# x-.net
KiCad netlist of a schematic drawn in Altium Designer
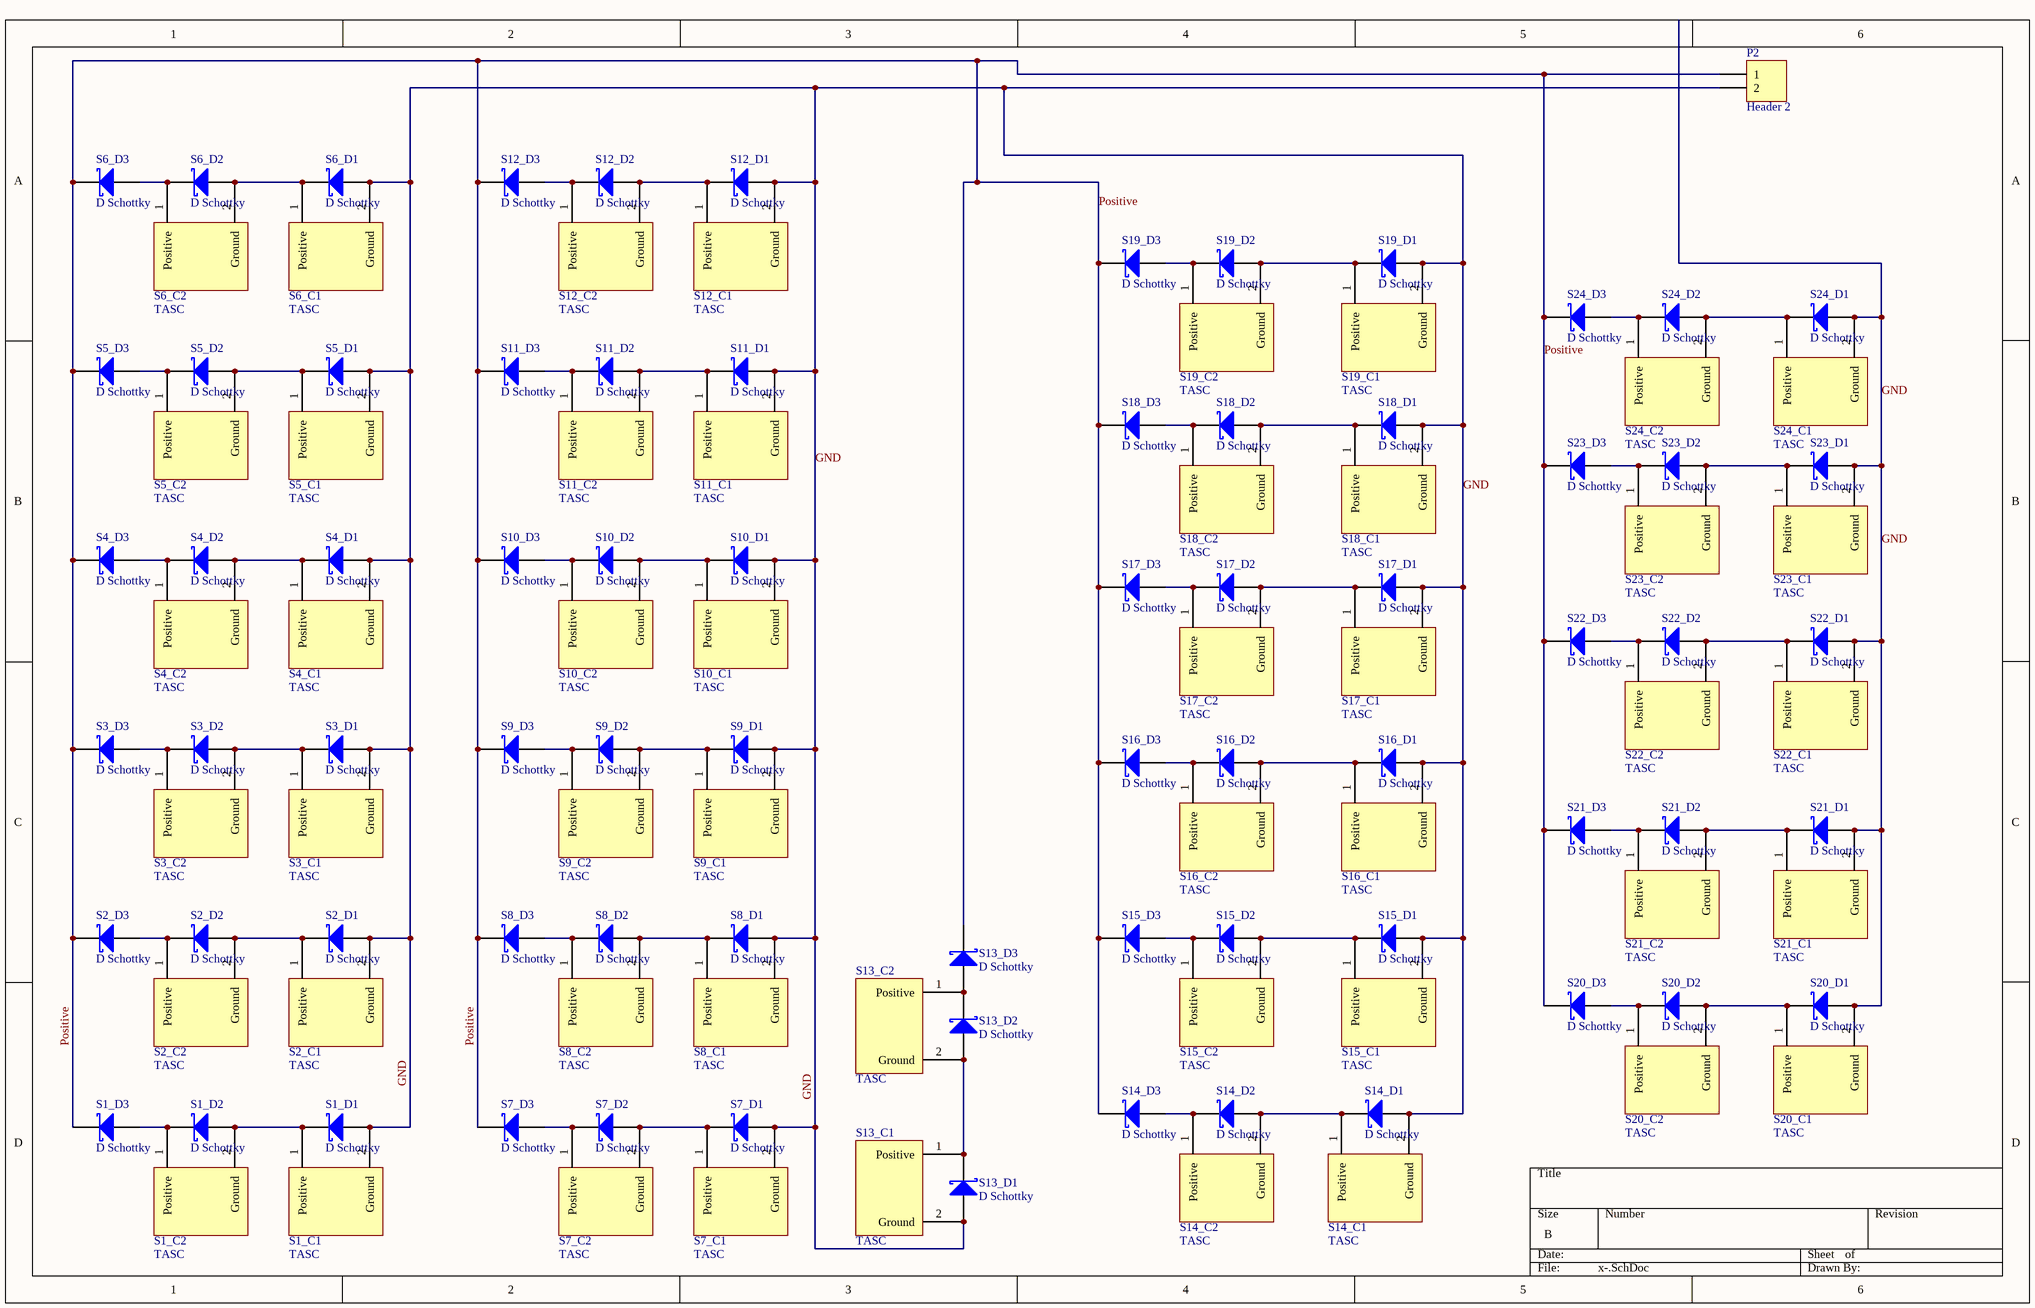
[diagram p0: x-.SchDoc]

(export (version "E")
  (design (tool "Eeschema 10.0.6"))
  (components
    (comp (ref "P2")
      (value "Header 2")
      (footprint "HDR1X2")
      (description "Header, 2-Pin")
      (fields (field (name "PUBLISHER") "Altium Limited"))
      (libsource (lib "Miscellaneous Connectors") (part "Header 2"))
    )
    (comp (ref "S1_C1")
      (value "TASC")
      (footprint "PCBComponent_1")
      (description "TASC Solar Cell")
      (libsource (lib "SolarPanel1") (part "TASC"))
    )
    (comp (ref "S1_C2")
      (value "TASC")
      (footprint "PCBComponent_1")
      (description "TASC Solar Cell")
      (libsource (lib "SolarPanel1") (part "TASC"))
    )
    (comp (ref "S1_D1")
      (value "D Schottky")
      (footprint "SMB")
      (description "Schottky Diode")
      (fields (field (name "PUBLISHER") "Altium Limited"))
      (libsource (lib "Miscellaneous Devices") (part "D Schottky"))
    )
    (comp (ref "S1_D2")
      (value "D Schottky")
      (footprint "SMB")
      (description "Schottky Diode")
      (fields (field (name "PUBLISHER") "Altium Limited"))
      (libsource (lib "Miscellaneous Devices") (part "D Schottky"))
    )
    (comp (ref "S1_D3")
      (value "D Schottky")
      (footprint "SMB")
      (description "Schottky Diode")
      (fields (field (name "PUBLISHER") "Altium Limited"))
      (libsource (lib "Miscellaneous Devices") (part "D Schottky"))
    )
    (comp (ref "S2_C1")
      (value "TASC")
      (footprint "PCBComponent_1")
      (description "TASC Solar Cell")
      (libsource (lib "SolarPanel1") (part "TASC"))
    )
    (comp (ref "S2_C2")
      (value "TASC")
      (footprint "PCBComponent_1")
      (description "TASC Solar Cell")
      (libsource (lib "SolarPanel1") (part "TASC"))
    )
    (comp (ref "S2_D1")
      (value "D Schottky")
      (footprint "SMB")
      (description "Schottky Diode")
      (fields (field (name "PUBLISHER") "Altium Limited"))
      (libsource (lib "Miscellaneous Devices") (part "D Schottky"))
    )
    (comp (ref "S2_D2")
      (value "D Schottky")
      (footprint "SMB")
      (description "Schottky Diode")
      (fields (field (name "PUBLISHER") "Altium Limited"))
      (libsource (lib "Miscellaneous Devices") (part "D Schottky"))
    )
    (comp (ref "S2_D3")
      (value "D Schottky")
      (footprint "SMB")
      (description "Schottky Diode")
      (fields (field (name "PUBLISHER") "Altium Limited"))
      (libsource (lib "Miscellaneous Devices") (part "D Schottky"))
    )
    (comp (ref "S3_C1")
      (value "TASC")
      (footprint "PCBComponent_1")
      (description "TASC Solar Cell")
      (libsource (lib "SolarPanel1") (part "TASC"))
    )
    (comp (ref "S3_C2")
      (value "TASC")
      (footprint "PCBComponent_1")
      (description "TASC Solar Cell")
      (libsource (lib "SolarPanel1") (part "TASC"))
    )
    (comp (ref "S3_D1")
      (value "D Schottky")
      (footprint "SMB")
      (description "Schottky Diode")
      (fields (field (name "PUBLISHER") "Altium Limited"))
      (libsource (lib "Miscellaneous Devices") (part "D Schottky"))
    )
    (comp (ref "S3_D2")
      (value "D Schottky")
      (footprint "SMB")
      (description "Schottky Diode")
      (fields (field (name "PUBLISHER") "Altium Limited"))
      (libsource (lib "Miscellaneous Devices") (part "D Schottky"))
    )
    (comp (ref "S3_D3")
      (value "D Schottky")
      (footprint "SMB")
      (description "Schottky Diode")
      (fields (field (name "PUBLISHER") "Altium Limited"))
      (libsource (lib "Miscellaneous Devices") (part "D Schottky"))
    )
    (comp (ref "S4_C1")
      (value "TASC")
      (footprint "PCBComponent_1")
      (description "TASC Solar Cell")
      (libsource (lib "SolarPanel1") (part "TASC"))
    )
    (comp (ref "S4_C2")
      (value "TASC")
      (footprint "PCBComponent_1")
      (description "TASC Solar Cell")
      (libsource (lib "SolarPanel1") (part "TASC"))
    )
    (comp (ref "S4_D1")
      (value "D Schottky")
      (footprint "SMB")
      (description "Schottky Diode")
      (fields (field (name "PUBLISHER") "Altium Limited"))
      (libsource (lib "Miscellaneous Devices") (part "D Schottky"))
    )
    (comp (ref "S4_D2")
      (value "D Schottky")
      (footprint "SMB")
      (description "Schottky Diode")
      (fields (field (name "PUBLISHER") "Altium Limited"))
      (libsource (lib "Miscellaneous Devices") (part "D Schottky"))
    )
    (comp (ref "S4_D3")
      (value "D Schottky")
      (footprint "SMB")
      (description "Schottky Diode")
      (fields (field (name "PUBLISHER") "Altium Limited"))
      (libsource (lib "Miscellaneous Devices") (part "D Schottky"))
    )
    (comp (ref "S5_C1")
      (value "TASC")
      (footprint "PCBComponent_1")
      (description "TASC Solar Cell")
      (libsource (lib "SolarPanel1") (part "TASC"))
    )
    (comp (ref "S5_C2")
      (value "TASC")
      (footprint "PCBComponent_1")
      (description "TASC Solar Cell")
      (libsource (lib "SolarPanel1") (part "TASC"))
    )
    (comp (ref "S5_D1")
      (value "D Schottky")
      (footprint "SMB")
      (description "Schottky Diode")
      (fields (field (name "PUBLISHER") "Altium Limited"))
      (libsource (lib "Miscellaneous Devices") (part "D Schottky"))
    )
    (comp (ref "S5_D2")
      (value "D Schottky")
      (footprint "SMB")
      (description "Schottky Diode")
      (fields (field (name "PUBLISHER") "Altium Limited"))
      (libsource (lib "Miscellaneous Devices") (part "D Schottky"))
    )
    (comp (ref "S5_D3")
      (value "D Schottky")
      (footprint "SMB")
      (description "Schottky Diode")
      (fields (field (name "PUBLISHER") "Altium Limited"))
      (libsource (lib "Miscellaneous Devices") (part "D Schottky"))
    )
    (comp (ref "S6_C1")
      (value "TASC")
      (footprint "PCBComponent_1")
      (description "TASC Solar Cell")
      (libsource (lib "SolarPanel1") (part "TASC"))
    )
    (comp (ref "S6_C2")
      (value "TASC")
      (footprint "PCBComponent_1")
      (description "TASC Solar Cell")
      (libsource (lib "SolarPanel1") (part "TASC"))
    )
    (comp (ref "S6_D1")
      (value "D Schottky")
      (footprint "SMB")
      (description "Schottky Diode")
      (fields (field (name "PUBLISHER") "Altium Limited"))
      (libsource (lib "Miscellaneous Devices") (part "D Schottky"))
    )
    (comp (ref "S6_D2")
      (value "D Schottky")
      (footprint "SMB")
      (description "Schottky Diode")
      (fields (field (name "PUBLISHER") "Altium Limited"))
      (libsource (lib "Miscellaneous Devices") (part "D Schottky"))
    )
    (comp (ref "S6_D3")
      (value "D Schottky")
      (footprint "SMB")
      (description "Schottky Diode")
      (fields (field (name "PUBLISHER") "Altium Limited"))
      (libsource (lib "Miscellaneous Devices") (part "D Schottky"))
    )
    (comp (ref "S7_C1")
      (value "TASC")
      (footprint "PCBComponent_1")
      (description "TASC Solar Cell")
      (libsource (lib "SolarPanel1") (part "TASC"))
    )
    (comp (ref "S7_C2")
      (value "TASC")
      (footprint "PCBComponent_1")
      (description "TASC Solar Cell")
      (libsource (lib "SolarPanel1") (part "TASC"))
    )
    (comp (ref "S7_D1")
      (value "D Schottky")
      (footprint "SMB")
      (description "Schottky Diode")
      (fields (field (name "PUBLISHER") "Altium Limited"))
      (libsource (lib "Miscellaneous Devices") (part "D Schottky"))
    )
    (comp (ref "S7_D2")
      (value "D Schottky")
      (footprint "SMB")
      (description "Schottky Diode")
      (fields (field (name "PUBLISHER") "Altium Limited"))
      (libsource (lib "Miscellaneous Devices") (part "D Schottky"))
    )
    (comp (ref "S7_D3")
      (value "D Schottky")
      (footprint "SMB")
      (description "Schottky Diode")
      (fields (field (name "PUBLISHER") "Altium Limited"))
      (libsource (lib "Miscellaneous Devices") (part "D Schottky"))
    )
    (comp (ref "S8_C1")
      (value "TASC")
      (footprint "PCBComponent_1")
      (description "TASC Solar Cell")
      (libsource (lib "SolarPanel1") (part "TASC"))
    )
    (comp (ref "S8_C2")
      (value "TASC")
      (footprint "PCBComponent_1")
      (description "TASC Solar Cell")
      (libsource (lib "SolarPanel1") (part "TASC"))
    )
    (comp (ref "S8_D1")
      (value "D Schottky")
      (footprint "SMB")
      (description "Schottky Diode")
      (fields (field (name "PUBLISHER") "Altium Limited"))
      (libsource (lib "Miscellaneous Devices") (part "D Schottky"))
    )
    (comp (ref "S8_D2")
      (value "D Schottky")
      (footprint "SMB")
      (description "Schottky Diode")
      (fields (field (name "PUBLISHER") "Altium Limited"))
      (libsource (lib "Miscellaneous Devices") (part "D Schottky"))
    )
    (comp (ref "S8_D3")
      (value "D Schottky")
      (footprint "SMB")
      (description "Schottky Diode")
      (fields (field (name "PUBLISHER") "Altium Limited"))
      (libsource (lib "Miscellaneous Devices") (part "D Schottky"))
    )
    (comp (ref "S9_C1")
      (value "TASC")
      (footprint "PCBComponent_1")
      (description "TASC Solar Cell")
      (libsource (lib "SolarPanel1") (part "TASC"))
    )
    (comp (ref "S9_C2")
      (value "TASC")
      (footprint "PCBComponent_1")
      (description "TASC Solar Cell")
      (libsource (lib "SolarPanel1") (part "TASC"))
    )
    (comp (ref "S9_D1")
      (value "D Schottky")
      (footprint "SMB")
      (description "Schottky Diode")
      (fields (field (name "PUBLISHER") "Altium Limited"))
      (libsource (lib "Miscellaneous Devices") (part "D Schottky"))
    )
    (comp (ref "S9_D2")
      (value "D Schottky")
      (footprint "SMB")
      (description "Schottky Diode")
      (fields (field (name "PUBLISHER") "Altium Limited"))
      (libsource (lib "Miscellaneous Devices") (part "D Schottky"))
    )
    (comp (ref "S9_D3")
      (value "D Schottky")
      (footprint "SMB")
      (description "Schottky Diode")
      (fields (field (name "PUBLISHER") "Altium Limited"))
      (libsource (lib "Miscellaneous Devices") (part "D Schottky"))
    )
    (comp (ref "S10_C1")
      (value "TASC")
      (footprint "PCBComponent_1")
      (description "TASC Solar Cell")
      (libsource (lib "SolarPanel1") (part "TASC"))
    )
    (comp (ref "S10_C2")
      (value "TASC")
      (footprint "PCBComponent_1")
      (description "TASC Solar Cell")
      (libsource (lib "SolarPanel1") (part "TASC"))
    )
    (comp (ref "S10_D1")
      (value "D Schottky")
      (footprint "SMB")
      (description "Schottky Diode")
      (fields (field (name "PUBLISHER") "Altium Limited"))
      (libsource (lib "Miscellaneous Devices") (part "D Schottky"))
    )
    (comp (ref "S10_D2")
      (value "D Schottky")
      (footprint "SMB")
      (description "Schottky Diode")
      (fields (field (name "PUBLISHER") "Altium Limited"))
      (libsource (lib "Miscellaneous Devices") (part "D Schottky"))
    )
    (comp (ref "S10_D3")
      (value "D Schottky")
      (footprint "SMB")
      (description "Schottky Diode")
      (fields (field (name "PUBLISHER") "Altium Limited"))
      (libsource (lib "Miscellaneous Devices") (part "D Schottky"))
    )
    (comp (ref "S11_C1")
      (value "TASC")
      (footprint "PCBComponent_1")
      (description "TASC Solar Cell")
      (libsource (lib "SolarPanel1") (part "TASC"))
    )
    (comp (ref "S11_C2")
      (value "TASC")
      (footprint "PCBComponent_1")
      (description "TASC Solar Cell")
      (libsource (lib "SolarPanel1") (part "TASC"))
    )
    (comp (ref "S11_D1")
      (value "D Schottky")
      (footprint "SMB")
      (description "Schottky Diode")
      (fields (field (name "PUBLISHER") "Altium Limited"))
      (libsource (lib "Miscellaneous Devices") (part "D Schottky"))
    )
    (comp (ref "S11_D2")
      (value "D Schottky")
      (footprint "SMB")
      (description "Schottky Diode")
      (fields (field (name "PUBLISHER") "Altium Limited"))
      (libsource (lib "Miscellaneous Devices") (part "D Schottky"))
    )
    (comp (ref "S11_D3")
      (value "D Schottky")
      (footprint "SMB")
      (description "Schottky Diode")
      (fields (field (name "PUBLISHER") "Altium Limited"))
      (libsource (lib "Miscellaneous Devices") (part "D Schottky"))
    )
    (comp (ref "S12_C1")
      (value "TASC")
      (footprint "PCBComponent_1")
      (description "TASC Solar Cell")
      (libsource (lib "SolarPanel1") (part "TASC"))
    )
    (comp (ref "S12_C2")
      (value "TASC")
      (footprint "PCBComponent_1")
      (description "TASC Solar Cell")
      (libsource (lib "SolarPanel1") (part "TASC"))
    )
    (comp (ref "S12_D1")
      (value "D Schottky")
      (footprint "SMB")
      (description "Schottky Diode")
      (fields (field (name "PUBLISHER") "Altium Limited"))
      (libsource (lib "Miscellaneous Devices") (part "D Schottky"))
    )
    (comp (ref "S12_D2")
      (value "D Schottky")
      (footprint "SMB")
      (description "Schottky Diode")
      (fields (field (name "PUBLISHER") "Altium Limited"))
      (libsource (lib "Miscellaneous Devices") (part "D Schottky"))
    )
    (comp (ref "S12_D3")
      (value "D Schottky")
      (footprint "SMB")
      (description "Schottky Diode")
      (fields (field (name "PUBLISHER") "Altium Limited"))
      (libsource (lib "Miscellaneous Devices") (part "D Schottky"))
    )
    (comp (ref "S13_C1")
      (value "TASC")
      (footprint "PCBComponent_1")
      (description "TASC Solar Cell")
      (libsource (lib "") (part "TASC_1"))
    )
    (comp (ref "S13_C2")
      (value "TASC")
      (footprint "PCBComponent_1")
      (description "TASC Solar Cell")
      (libsource (lib "") (part "TASC_1"))
    )
    (comp (ref "S13_D1")
      (value "D Schottky")
      (footprint "SMB")
      (description "Schottky Diode")
      (fields (field (name "PUBLISHER") "Altium Limited"))
      (libsource (lib "Miscellaneous Devices") (part "D Schottky"))
    )
    (comp (ref "S13_D2")
      (value "D Schottky")
      (footprint "SMB")
      (description "Schottky Diode")
      (fields (field (name "PUBLISHER") "Altium Limited"))
      (libsource (lib "Miscellaneous Devices") (part "D Schottky"))
    )
    (comp (ref "S13_D3")
      (value "D Schottky")
      (footprint "SMB")
      (description "Schottky Diode")
      (fields (field (name "PUBLISHER") "Altium Limited"))
      (libsource (lib "Miscellaneous Devices") (part "D Schottky"))
    )
    (comp (ref "S14_C1")
      (value "TASC")
      (footprint "PCBComponent_1")
      (description "TASC Solar Cell")
      (libsource (lib "SolarPanel1") (part "TASC"))
    )
    (comp (ref "S14_C2")
      (value "TASC")
      (footprint "PCBComponent_1")
      (description "TASC Solar Cell")
      (libsource (lib "SolarPanel1") (part "TASC"))
    )
    (comp (ref "S14_D1")
      (value "D Schottky")
      (footprint "SMB")
      (description "Schottky Diode")
      (fields (field (name "PUBLISHER") "Altium Limited"))
      (libsource (lib "Miscellaneous Devices") (part "D Schottky"))
    )
    (comp (ref "S14_D2")
      (value "D Schottky")
      (footprint "SMB")
      (description "Schottky Diode")
      (fields (field (name "PUBLISHER") "Altium Limited"))
      (libsource (lib "Miscellaneous Devices") (part "D Schottky"))
    )
    (comp (ref "S14_D3")
      (value "D Schottky")
      (footprint "SMB")
      (description "Schottky Diode")
      (fields (field (name "PUBLISHER") "Altium Limited"))
      (libsource (lib "Miscellaneous Devices") (part "D Schottky"))
    )
    (comp (ref "S15_C1")
      (value "TASC")
      (footprint "PCBComponent_1")
      (description "TASC Solar Cell")
      (libsource (lib "SolarPanel1") (part "TASC"))
    )
    (comp (ref "S15_C2")
      (value "TASC")
      (footprint "PCBComponent_1")
      (description "TASC Solar Cell")
      (libsource (lib "SolarPanel1") (part "TASC"))
    )
    (comp (ref "S15_D1")
      (value "D Schottky")
      (footprint "SMB")
      (description "Schottky Diode")
      (fields (field (name "PUBLISHER") "Altium Limited"))
      (libsource (lib "Miscellaneous Devices") (part "D Schottky"))
    )
    (comp (ref "S15_D2")
      (value "D Schottky")
      (footprint "SMB")
      (description "Schottky Diode")
      (fields (field (name "PUBLISHER") "Altium Limited"))
      (libsource (lib "Miscellaneous Devices") (part "D Schottky"))
    )
    (comp (ref "S15_D3")
      (value "D Schottky")
      (footprint "SMB")
      (description "Schottky Diode")
      (fields (field (name "PUBLISHER") "Altium Limited"))
      (libsource (lib "Miscellaneous Devices") (part "D Schottky"))
    )
    (comp (ref "S16_C1")
      (value "TASC")
      (footprint "PCBComponent_1")
      (description "TASC Solar Cell")
      (libsource (lib "SolarPanel1") (part "TASC"))
    )
    (comp (ref "S16_C2")
      (value "TASC")
      (footprint "PCBComponent_1")
      (description "TASC Solar Cell")
      (libsource (lib "SolarPanel1") (part "TASC"))
    )
    (comp (ref "S16_D1")
      (value "D Schottky")
      (footprint "SMB")
      (description "Schottky Diode")
      (fields (field (name "PUBLISHER") "Altium Limited"))
      (libsource (lib "Miscellaneous Devices") (part "D Schottky"))
    )
    (comp (ref "S16_D2")
      (value "D Schottky")
      (footprint "SMB")
      (description "Schottky Diode")
      (fields (field (name "PUBLISHER") "Altium Limited"))
      (libsource (lib "Miscellaneous Devices") (part "D Schottky"))
    )
    (comp (ref "S16_D3")
      (value "D Schottky")
      (footprint "SMB")
      (description "Schottky Diode")
      (fields (field (name "PUBLISHER") "Altium Limited"))
      (libsource (lib "Miscellaneous Devices") (part "D Schottky"))
    )
    (comp (ref "S17_C1")
      (value "TASC")
      (footprint "PCBComponent_1")
      (description "TASC Solar Cell")
      (libsource (lib "SolarPanel1") (part "TASC"))
    )
    (comp (ref "S17_C2")
      (value "TASC")
      (footprint "PCBComponent_1")
      (description "TASC Solar Cell")
      (libsource (lib "SolarPanel1") (part "TASC"))
    )
    (comp (ref "S17_D1")
      (value "D Schottky")
      (footprint "SMB")
      (description "Schottky Diode")
      (fields (field (name "PUBLISHER") "Altium Limited"))
      (libsource (lib "Miscellaneous Devices") (part "D Schottky"))
    )
    (comp (ref "S17_D2")
      (value "D Schottky")
      (footprint "SMB")
      (description "Schottky Diode")
      (fields (field (name "PUBLISHER") "Altium Limited"))
      (libsource (lib "Miscellaneous Devices") (part "D Schottky"))
    )
    (comp (ref "S17_D3")
      (value "D Schottky")
      (footprint "SMB")
      (description "Schottky Diode")
      (fields (field (name "PUBLISHER") "Altium Limited"))
      (libsource (lib "Miscellaneous Devices") (part "D Schottky"))
    )
    (comp (ref "S18_C1")
      (value "TASC")
      (footprint "PCBComponent_1")
      (description "TASC Solar Cell")
      (libsource (lib "SolarPanel1") (part "TASC"))
    )
    (comp (ref "S18_C2")
      (value "TASC")
      (footprint "PCBComponent_1")
      (description "TASC Solar Cell")
      (libsource (lib "SolarPanel1") (part "TASC"))
    )
    (comp (ref "S18_D1")
      (value "D Schottky")
      (footprint "SMB")
      (description "Schottky Diode")
      (fields (field (name "PUBLISHER") "Altium Limited"))
      (libsource (lib "Miscellaneous Devices") (part "D Schottky"))
    )
    (comp (ref "S18_D2")
      (value "D Schottky")
      (footprint "SMB")
      (description "Schottky Diode")
      (fields (field (name "PUBLISHER") "Altium Limited"))
      (libsource (lib "Miscellaneous Devices") (part "D Schottky"))
    )
    (comp (ref "S18_D3")
      (value "D Schottky")
      (footprint "SMB")
      (description "Schottky Diode")
      (fields (field (name "PUBLISHER") "Altium Limited"))
      (libsource (lib "Miscellaneous Devices") (part "D Schottky"))
    )
    (comp (ref "S19_C1")
      (value "TASC")
      (footprint "PCBComponent_1")
      (description "TASC Solar Cell")
      (libsource (lib "SolarPanel1") (part "TASC"))
    )
    (comp (ref "S19_C2")
      (value "TASC")
      (footprint "PCBComponent_1")
      (description "TASC Solar Cell")
      (libsource (lib "SolarPanel1") (part "TASC"))
    )
    (comp (ref "S19_D1")
      (value "D Schottky")
      (footprint "SMB")
      (description "Schottky Diode")
      (fields (field (name "PUBLISHER") "Altium Limited"))
      (libsource (lib "Miscellaneous Devices") (part "D Schottky"))
    )
    (comp (ref "S19_D2")
      (value "D Schottky")
      (footprint "SMB")
      (description "Schottky Diode")
      (fields (field (name "PUBLISHER") "Altium Limited"))
      (libsource (lib "Miscellaneous Devices") (part "D Schottky"))
    )
    (comp (ref "S19_D3")
      (value "D Schottky")
      (footprint "SMB")
      (description "Schottky Diode")
      (fields (field (name "PUBLISHER") "Altium Limited"))
      (libsource (lib "Miscellaneous Devices") (part "D Schottky"))
    )
    (comp (ref "S20_C1")
      (value "TASC")
      (footprint "PCBComponent_1")
      (description "TASC Solar Cell")
      (libsource (lib "SolarPanel1") (part "TASC"))
    )
    (comp (ref "S20_C2")
      (value "TASC")
      (footprint "PCBComponent_1")
      (description "TASC Solar Cell")
      (libsource (lib "SolarPanel1") (part "TASC"))
    )
    (comp (ref "S20_D1")
      (value "D Schottky")
      (footprint "SMB")
      (description "Schottky Diode")
      (fields (field (name "PUBLISHER") "Altium Limited"))
      (libsource (lib "Miscellaneous Devices") (part "D Schottky"))
    )
    (comp (ref "S20_D2")
      (value "D Schottky")
      (footprint "SMB")
      (description "Schottky Diode")
      (fields (field (name "PUBLISHER") "Altium Limited"))
      (libsource (lib "Miscellaneous Devices") (part "D Schottky"))
    )
    (comp (ref "S20_D3")
      (value "D Schottky")
      (footprint "SMB")
      (description "Schottky Diode")
      (fields (field (name "PUBLISHER") "Altium Limited"))
      (libsource (lib "Miscellaneous Devices") (part "D Schottky"))
    )
    (comp (ref "S21_C1")
      (value "TASC")
      (footprint "PCBComponent_1")
      (description "TASC Solar Cell")
      (libsource (lib "SolarPanel1") (part "TASC"))
    )
    (comp (ref "S21_C2")
      (value "TASC")
      (footprint "PCBComponent_1")
      (description "TASC Solar Cell")
      (libsource (lib "SolarPanel1") (part "TASC"))
    )
    (comp (ref "S21_D1")
      (value "D Schottky")
      (footprint "SMB")
      (description "Schottky Diode")
      (fields (field (name "PUBLISHER") "Altium Limited"))
      (libsource (lib "Miscellaneous Devices") (part "D Schottky"))
    )
    (comp (ref "S21_D2")
      (value "D Schottky")
      (footprint "SMB")
      (description "Schottky Diode")
      (fields (field (name "PUBLISHER") "Altium Limited"))
      (libsource (lib "Miscellaneous Devices") (part "D Schottky"))
    )
    (comp (ref "S21_D3")
      (value "D Schottky")
      (footprint "SMB")
      (description "Schottky Diode")
      (fields (field (name "PUBLISHER") "Altium Limited"))
      (libsource (lib "Miscellaneous Devices") (part "D Schottky"))
    )
    (comp (ref "S22_C1")
      (value "TASC")
      (footprint "PCBComponent_1")
      (description "TASC Solar Cell")
      (libsource (lib "SolarPanel1") (part "TASC"))
    )
    (comp (ref "S22_C2")
      (value "TASC")
      (footprint "PCBComponent_1")
      (description "TASC Solar Cell")
      (libsource (lib "SolarPanel1") (part "TASC"))
    )
    (comp (ref "S22_D1")
      (value "D Schottky")
      (footprint "SMB")
      (description "Schottky Diode")
      (fields (field (name "PUBLISHER") "Altium Limited"))
      (libsource (lib "Miscellaneous Devices") (part "D Schottky"))
    )
    (comp (ref "S22_D2")
      (value "D Schottky")
      (footprint "SMB")
      (description "Schottky Diode")
      (fields (field (name "PUBLISHER") "Altium Limited"))
      (libsource (lib "Miscellaneous Devices") (part "D Schottky"))
    )
    (comp (ref "S22_D3")
      (value "D Schottky")
      (footprint "SMB")
      (description "Schottky Diode")
      (fields (field (name "PUBLISHER") "Altium Limited"))
      (libsource (lib "Miscellaneous Devices") (part "D Schottky"))
    )
    (comp (ref "S23_C1")
      (value "TASC")
      (footprint "PCBComponent_1")
      (description "TASC Solar Cell")
      (libsource (lib "SolarPanel1") (part "TASC"))
    )
    (comp (ref "S23_C2")
      (value "TASC")
      (footprint "PCBComponent_1")
      (description "TASC Solar Cell")
      (libsource (lib "SolarPanel1") (part "TASC"))
    )
    (comp (ref "S23_D1")
      (value "D Schottky")
      (footprint "SMB")
      (description "Schottky Diode")
      (fields (field (name "PUBLISHER") "Altium Limited"))
      (libsource (lib "Miscellaneous Devices") (part "D Schottky"))
    )
    (comp (ref "S23_D2")
      (value "D Schottky")
      (footprint "SMB")
      (description "Schottky Diode")
      (fields (field (name "PUBLISHER") "Altium Limited"))
      (libsource (lib "Miscellaneous Devices") (part "D Schottky"))
    )
    (comp (ref "S23_D3")
      (value "D Schottky")
      (footprint "SMB")
      (description "Schottky Diode")
      (fields (field (name "PUBLISHER") "Altium Limited"))
      (libsource (lib "Miscellaneous Devices") (part "D Schottky"))
    )
    (comp (ref "S24_C1")
      (value "TASC")
      (footprint "PCBComponent_1")
      (description "TASC Solar Cell")
      (libsource (lib "SolarPanel1") (part "TASC"))
    )
    (comp (ref "S24_C2")
      (value "TASC")
      (footprint "PCBComponent_1")
      (description "TASC Solar Cell")
      (libsource (lib "SolarPanel1") (part "TASC"))
    )
    (comp (ref "S24_D1")
      (value "D Schottky")
      (footprint "SMB")
      (description "Schottky Diode")
      (fields (field (name "PUBLISHER") "Altium Limited"))
      (libsource (lib "Miscellaneous Devices") (part "D Schottky"))
    )
    (comp (ref "S24_D2")
      (value "D Schottky")
      (footprint "SMB")
      (description "Schottky Diode")
      (fields (field (name "PUBLISHER") "Altium Limited"))
      (libsource (lib "Miscellaneous Devices") (part "D Schottky"))
    )
    (comp (ref "S24_D3")
      (value "D Schottky")
      (footprint "SMB")
      (description "Schottky Diode")
      (fields (field (name "PUBLISHER") "Altium Limited"))
      (libsource (lib "Miscellaneous Devices") (part "D Schottky"))
    )
  )
  (nets
    (net (code "1") (name "/GND") (class "Default")
      (node (ref "P2") (pin "2") (pinfunction "2_2") (pintype "passive"))
      (node (ref "S10_C1") (pin "2") (pinfunction "Ground_2") (pintype "power_in"))
      (node (ref "S10_D1") (pin "1") (pinfunction "A_1") (pintype "passive"))
      (node (ref "S11_C1") (pin "2") (pinfunction "Ground_2") (pintype "power_in"))
      (node (ref "S11_D1") (pin "1") (pinfunction "A_1") (pintype "passive"))
      (node (ref "S12_C1") (pin "2") (pinfunction "Ground_2") (pintype "power_in"))
      (node (ref "S12_D1") (pin "1") (pinfunction "A_1") (pintype "passive"))
      (node (ref "S13_C1") (pin "2") (pinfunction "Ground_2") (pintype "power_in"))
      (node (ref "S13_D1") (pin "1") (pinfunction "A_1") (pintype "passive"))
      (node (ref "S14_C1") (pin "2") (pinfunction "Ground_2") (pintype "power_in"))
      (node (ref "S14_D1") (pin "1") (pinfunction "A_1") (pintype "passive"))
      (node (ref "S15_C1") (pin "2") (pinfunction "Ground_2") (pintype "power_in"))
      (node (ref "S15_D1") (pin "1") (pinfunction "A_1") (pintype "passive"))
      (node (ref "S16_C1") (pin "2") (pinfunction "Ground_2") (pintype "power_in"))
      (node (ref "S16_D1") (pin "1") (pinfunction "A_1") (pintype "passive"))
      (node (ref "S17_C1") (pin "2") (pinfunction "Ground_2") (pintype "power_in"))
      (node (ref "S17_D1") (pin "1") (pinfunction "A_1") (pintype "passive"))
      (node (ref "S18_C1") (pin "2") (pinfunction "Ground_2") (pintype "power_in"))
      (node (ref "S18_D1") (pin "1") (pinfunction "A_1") (pintype "passive"))
      (node (ref "S19_C1") (pin "2") (pinfunction "Ground_2") (pintype "power_in"))
      (node (ref "S19_D1") (pin "1") (pinfunction "A_1") (pintype "passive"))
      (node (ref "S1_C1") (pin "2") (pinfunction "Ground_2") (pintype "power_in"))
      (node (ref "S1_D1") (pin "1") (pinfunction "A_1") (pintype "passive"))
      (node (ref "S20_C1") (pin "2") (pinfunction "Ground_2") (pintype "power_in"))
      (node (ref "S20_D1") (pin "1") (pinfunction "A_1") (pintype "passive"))
      (node (ref "S21_C1") (pin "2") (pinfunction "Ground_2") (pintype "power_in"))
      (node (ref "S21_D1") (pin "1") (pinfunction "A_1") (pintype "passive"))
      (node (ref "S22_C1") (pin "2") (pinfunction "Ground_2") (pintype "power_in"))
      (node (ref "S22_D1") (pin "1") (pinfunction "A_1") (pintype "passive"))
      (node (ref "S23_C1") (pin "2") (pinfunction "Ground_2") (pintype "power_in"))
      (node (ref "S23_D1") (pin "1") (pinfunction "A_1") (pintype "passive"))
      (node (ref "S24_C1") (pin "2") (pinfunction "Ground_2") (pintype "power_in"))
      (node (ref "S24_D1") (pin "1") (pinfunction "A_1") (pintype "passive"))
      (node (ref "S2_C1") (pin "2") (pinfunction "Ground_2") (pintype "power_in"))
      (node (ref "S2_D1") (pin "1") (pinfunction "A_1") (pintype "passive"))
      (node (ref "S3_C1") (pin "2") (pinfunction "Ground_2") (pintype "power_in"))
      (node (ref "S3_D1") (pin "1") (pinfunction "A_1") (pintype "passive"))
      (node (ref "S4_C1") (pin "2") (pinfunction "Ground_2") (pintype "power_in"))
      (node (ref "S4_D1") (pin "1") (pinfunction "A_1") (pintype "passive"))
      (node (ref "S5_C1") (pin "2") (pinfunction "Ground_2") (pintype "power_in"))
      (node (ref "S5_D1") (pin "1") (pinfunction "A_1") (pintype "passive"))
      (node (ref "S6_C1") (pin "2") (pinfunction "Ground_2") (pintype "power_in"))
      (node (ref "S6_D1") (pin "1") (pinfunction "A_1") (pintype "passive"))
      (node (ref "S7_C1") (pin "2") (pinfunction "Ground_2") (pintype "power_in"))
      (node (ref "S7_D1") (pin "1") (pinfunction "A_1") (pintype "passive"))
      (node (ref "S8_C1") (pin "2") (pinfunction "Ground_2") (pintype "power_in"))
      (node (ref "S8_D1") (pin "1") (pinfunction "A_1") (pintype "passive"))
      (node (ref "S9_C1") (pin "2") (pinfunction "Ground_2") (pintype "power_in"))
      (node (ref "S9_D1") (pin "1") (pinfunction "A_1") (pintype "passive"))
    )
    (net (code "2") (name "/Positive") (class "Default")
      (node (ref "P2") (pin "1") (pinfunction "1_1") (pintype "passive"))
      (node (ref "S10_D3") (pin "2") (pinfunction "K_2") (pintype "passive"))
      (node (ref "S11_D3") (pin "2") (pinfunction "K_2") (pintype "passive"))
      (node (ref "S12_D3") (pin "2") (pinfunction "K_2") (pintype "passive"))
      (node (ref "S13_D3") (pin "2") (pinfunction "K_2") (pintype "passive"))
      (node (ref "S14_D3") (pin "2") (pinfunction "K_2") (pintype "passive"))
      (node (ref "S15_D3") (pin "2") (pinfunction "K_2") (pintype "passive"))
      (node (ref "S16_D3") (pin "2") (pinfunction "K_2") (pintype "passive"))
      (node (ref "S17_D3") (pin "2") (pinfunction "K_2") (pintype "passive"))
      (node (ref "S18_D3") (pin "2") (pinfunction "K_2") (pintype "passive"))
      (node (ref "S19_D3") (pin "2") (pinfunction "K_2") (pintype "passive"))
      (node (ref "S1_D3") (pin "2") (pinfunction "K_2") (pintype "passive"))
      (node (ref "S20_D3") (pin "2") (pinfunction "K_2") (pintype "passive"))
      (node (ref "S21_D3") (pin "2") (pinfunction "K_2") (pintype "passive"))
      (node (ref "S22_D3") (pin "2") (pinfunction "K_2") (pintype "passive"))
      (node (ref "S23_D3") (pin "2") (pinfunction "K_2") (pintype "passive"))
      (node (ref "S24_D3") (pin "2") (pinfunction "K_2") (pintype "passive"))
      (node (ref "S2_D3") (pin "2") (pinfunction "K_2") (pintype "passive"))
      (node (ref "S3_D3") (pin "2") (pinfunction "K_2") (pintype "passive"))
      (node (ref "S4_D3") (pin "2") (pinfunction "K_2") (pintype "passive"))
      (node (ref "S5_D3") (pin "2") (pinfunction "K_2") (pintype "passive"))
      (node (ref "S6_D3") (pin "2") (pinfunction "K_2") (pintype "passive"))
      (node (ref "S7_D3") (pin "2") (pinfunction "K_2") (pintype "passive"))
      (node (ref "S8_D3") (pin "2") (pinfunction "K_2") (pintype "passive"))
      (node (ref "S9_D3") (pin "2") (pinfunction "K_2") (pintype "passive"))
    )
    (net (code "3") (name "Net-(S1_C1-Positive)") (class "Default")
      (node (ref "S1_C1") (pin "1") (pinfunction "Positive_1") (pintype "power_in"))
      (node (ref "S1_C2") (pin "2") (pinfunction "Ground_2") (pintype "power_in"))
      (node (ref "S1_D1") (pin "2") (pinfunction "K_2") (pintype "passive"))
      (node (ref "S1_D2") (pin "1") (pinfunction "A_1") (pintype "passive"))
    )
    (net (code "4") (name "Net-(S1_C2-Positive)") (class "Default")
      (node (ref "S1_C2") (pin "1") (pinfunction "Positive_1") (pintype "power_in"))
      (node (ref "S1_D2") (pin "2") (pinfunction "K_2") (pintype "passive"))
      (node (ref "S1_D3") (pin "1") (pinfunction "A_1") (pintype "passive"))
    )
    (net (code "5") (name "Net-(S2_C1-Positive)") (class "Default")
      (node (ref "S2_C1") (pin "1") (pinfunction "Positive_1") (pintype "power_in"))
      (node (ref "S2_C2") (pin "2") (pinfunction "Ground_2") (pintype "power_in"))
      (node (ref "S2_D1") (pin "2") (pinfunction "K_2") (pintype "passive"))
      (node (ref "S2_D2") (pin "1") (pinfunction "A_1") (pintype "passive"))
    )
    (net (code "6") (name "Net-(S2_C2-Positive)") (class "Default")
      (node (ref "S2_C2") (pin "1") (pinfunction "Positive_1") (pintype "power_in"))
      (node (ref "S2_D2") (pin "2") (pinfunction "K_2") (pintype "passive"))
      (node (ref "S2_D3") (pin "1") (pinfunction "A_1") (pintype "passive"))
    )
    (net (code "7") (name "Net-(S3_C1-Positive)") (class "Default")
      (node (ref "S3_C1") (pin "1") (pinfunction "Positive_1") (pintype "power_in"))
      (node (ref "S3_C2") (pin "2") (pinfunction "Ground_2") (pintype "power_in"))
      (node (ref "S3_D1") (pin "2") (pinfunction "K_2") (pintype "passive"))
      (node (ref "S3_D2") (pin "1") (pinfunction "A_1") (pintype "passive"))
    )
    (net (code "8") (name "Net-(S3_C2-Positive)") (class "Default")
      (node (ref "S3_C2") (pin "1") (pinfunction "Positive_1") (pintype "power_in"))
      (node (ref "S3_D2") (pin "2") (pinfunction "K_2") (pintype "passive"))
      (node (ref "S3_D3") (pin "1") (pinfunction "A_1") (pintype "passive"))
    )
    (net (code "9") (name "Net-(S4_C1-Positive)") (class "Default")
      (node (ref "S4_C1") (pin "1") (pinfunction "Positive_1") (pintype "power_in"))
      (node (ref "S4_C2") (pin "2") (pinfunction "Ground_2") (pintype "power_in"))
      (node (ref "S4_D1") (pin "2") (pinfunction "K_2") (pintype "passive"))
      (node (ref "S4_D2") (pin "1") (pinfunction "A_1") (pintype "passive"))
    )
    (net (code "10") (name "Net-(S4_C2-Positive)") (class "Default")
      (node (ref "S4_C2") (pin "1") (pinfunction "Positive_1") (pintype "power_in"))
      (node (ref "S4_D2") (pin "2") (pinfunction "K_2") (pintype "passive"))
      (node (ref "S4_D3") (pin "1") (pinfunction "A_1") (pintype "passive"))
    )
    (net (code "11") (name "Net-(S5_C1-Positive)") (class "Default")
      (node (ref "S5_C1") (pin "1") (pinfunction "Positive_1") (pintype "power_in"))
      (node (ref "S5_C2") (pin "2") (pinfunction "Ground_2") (pintype "power_in"))
      (node (ref "S5_D1") (pin "2") (pinfunction "K_2") (pintype "passive"))
      (node (ref "S5_D2") (pin "1") (pinfunction "A_1") (pintype "passive"))
    )
    (net (code "12") (name "Net-(S5_C2-Positive)") (class "Default")
      (node (ref "S5_C2") (pin "1") (pinfunction "Positive_1") (pintype "power_in"))
      (node (ref "S5_D2") (pin "2") (pinfunction "K_2") (pintype "passive"))
      (node (ref "S5_D3") (pin "1") (pinfunction "A_1") (pintype "passive"))
    )
    (net (code "13") (name "Net-(S6_C1-Positive)") (class "Default")
      (node (ref "S6_C1") (pin "1") (pinfunction "Positive_1") (pintype "power_in"))
      (node (ref "S6_C2") (pin "2") (pinfunction "Ground_2") (pintype "power_in"))
      (node (ref "S6_D1") (pin "2") (pinfunction "K_2") (pintype "passive"))
      (node (ref "S6_D2") (pin "1") (pinfunction "A_1") (pintype "passive"))
    )
    (net (code "14") (name "Net-(S6_C2-Positive)") (class "Default")
      (node (ref "S6_C2") (pin "1") (pinfunction "Positive_1") (pintype "power_in"))
      (node (ref "S6_D2") (pin "2") (pinfunction "K_2") (pintype "passive"))
      (node (ref "S6_D3") (pin "1") (pinfunction "A_1") (pintype "passive"))
    )
    (net (code "15") (name "Net-(S7_C1-Positive)") (class "Default")
      (node (ref "S7_C1") (pin "1") (pinfunction "Positive_1") (pintype "power_in"))
      (node (ref "S7_C2") (pin "2") (pinfunction "Ground_2") (pintype "power_in"))
      (node (ref "S7_D1") (pin "2") (pinfunction "K_2") (pintype "passive"))
      (node (ref "S7_D2") (pin "1") (pinfunction "A_1") (pintype "passive"))
    )
    (net (code "16") (name "Net-(S7_C2-Positive)") (class "Default")
      (node (ref "S7_C2") (pin "1") (pinfunction "Positive_1") (pintype "power_in"))
      (node (ref "S7_D2") (pin "2") (pinfunction "K_2") (pintype "passive"))
      (node (ref "S7_D3") (pin "1") (pinfunction "A_1") (pintype "passive"))
    )
    (net (code "17") (name "Net-(S8_C1-Positive)") (class "Default")
      (node (ref "S8_C1") (pin "1") (pinfunction "Positive_1") (pintype "power_in"))
      (node (ref "S8_C2") (pin "2") (pinfunction "Ground_2") (pintype "power_in"))
      (node (ref "S8_D1") (pin "2") (pinfunction "K_2") (pintype "passive"))
      (node (ref "S8_D2") (pin "1") (pinfunction "A_1") (pintype "passive"))
    )
    (net (code "18") (name "Net-(S8_C2-Positive)") (class "Default")
      (node (ref "S8_C2") (pin "1") (pinfunction "Positive_1") (pintype "power_in"))
      (node (ref "S8_D2") (pin "2") (pinfunction "K_2") (pintype "passive"))
      (node (ref "S8_D3") (pin "1") (pinfunction "A_1") (pintype "passive"))
    )
    (net (code "19") (name "Net-(S9_C1-Positive)") (class "Default")
      (node (ref "S9_C1") (pin "1") (pinfunction "Positive_1") (pintype "power_in"))
      (node (ref "S9_C2") (pin "2") (pinfunction "Ground_2") (pintype "power_in"))
      (node (ref "S9_D1") (pin "2") (pinfunction "K_2") (pintype "passive"))
      (node (ref "S9_D2") (pin "1") (pinfunction "A_1") (pintype "passive"))
    )
    (net (code "20") (name "Net-(S9_C2-Positive)") (class "Default")
      (node (ref "S9_C2") (pin "1") (pinfunction "Positive_1") (pintype "power_in"))
      (node (ref "S9_D2") (pin "2") (pinfunction "K_2") (pintype "passive"))
      (node (ref "S9_D3") (pin "1") (pinfunction "A_1") (pintype "passive"))
    )
    (net (code "21") (name "Net-(S10_C1-Positive)") (class "Default")
      (node (ref "S10_C1") (pin "1") (pinfunction "Positive_1") (pintype "power_in"))
      (node (ref "S10_C2") (pin "2") (pinfunction "Ground_2") (pintype "power_in"))
      (node (ref "S10_D1") (pin "2") (pinfunction "K_2") (pintype "passive"))
      (node (ref "S10_D2") (pin "1") (pinfunction "A_1") (pintype "passive"))
    )
    (net (code "22") (name "Net-(S10_C2-Positive)") (class "Default")
      (node (ref "S10_C2") (pin "1") (pinfunction "Positive_1") (pintype "power_in"))
      (node (ref "S10_D2") (pin "2") (pinfunction "K_2") (pintype "passive"))
      (node (ref "S10_D3") (pin "1") (pinfunction "A_1") (pintype "passive"))
    )
    (net (code "23") (name "Net-(S11_C1-Positive)") (class "Default")
      (node (ref "S11_C1") (pin "1") (pinfunction "Positive_1") (pintype "power_in"))
      (node (ref "S11_C2") (pin "2") (pinfunction "Ground_2") (pintype "power_in"))
      (node (ref "S11_D1") (pin "2") (pinfunction "K_2") (pintype "passive"))
      (node (ref "S11_D2") (pin "1") (pinfunction "A_1") (pintype "passive"))
    )
    (net (code "24") (name "Net-(S11_C2-Positive)") (class "Default")
      (node (ref "S11_C2") (pin "1") (pinfunction "Positive_1") (pintype "power_in"))
      (node (ref "S11_D2") (pin "2") (pinfunction "K_2") (pintype "passive"))
      (node (ref "S11_D3") (pin "1") (pinfunction "A_1") (pintype "passive"))
    )
    (net (code "25") (name "Net-(S12_C1-Positive)") (class "Default")
      (node (ref "S12_C1") (pin "1") (pinfunction "Positive_1") (pintype "power_in"))
      (node (ref "S12_C2") (pin "2") (pinfunction "Ground_2") (pintype "power_in"))
      (node (ref "S12_D1") (pin "2") (pinfunction "K_2") (pintype "passive"))
      (node (ref "S12_D2") (pin "1") (pinfunction "A_1") (pintype "passive"))
    )
    (net (code "26") (name "Net-(S12_C2-Positive)") (class "Default")
      (node (ref "S12_C2") (pin "1") (pinfunction "Positive_1") (pintype "power_in"))
      (node (ref "S12_D2") (pin "2") (pinfunction "K_2") (pintype "passive"))
      (node (ref "S12_D3") (pin "1") (pinfunction "A_1") (pintype "passive"))
    )
    (net (code "27") (name "Net-(S13_C1-Positive)") (class "Default")
      (node (ref "S13_C1") (pin "1") (pinfunction "Positive_1") (pintype "power_in"))
      (node (ref "S13_C2") (pin "2") (pinfunction "Ground_2") (pintype "power_in"))
      (node (ref "S13_D1") (pin "2") (pinfunction "K_2") (pintype "passive"))
      (node (ref "S13_D2") (pin "1") (pinfunction "A_1") (pintype "passive"))
    )
    (net (code "28") (name "Net-(S13_C2-Positive)") (class "Default")
      (node (ref "S13_C2") (pin "1") (pinfunction "Positive_1") (pintype "power_in"))
      (node (ref "S13_D2") (pin "2") (pinfunction "K_2") (pintype "passive"))
      (node (ref "S13_D3") (pin "1") (pinfunction "A_1") (pintype "passive"))
    )
    (net (code "29") (name "Net-(S14_C1-Positive)") (class "Default")
      (node (ref "S14_C1") (pin "1") (pinfunction "Positive_1") (pintype "power_in"))
      (node (ref "S14_C2") (pin "2") (pinfunction "Ground_2") (pintype "power_in"))
      (node (ref "S14_D1") (pin "2") (pinfunction "K_2") (pintype "passive"))
      (node (ref "S14_D2") (pin "1") (pinfunction "A_1") (pintype "passive"))
    )
    (net (code "30") (name "Net-(S14_C2-Positive)") (class "Default")
      (node (ref "S14_C2") (pin "1") (pinfunction "Positive_1") (pintype "power_in"))
      (node (ref "S14_D2") (pin "2") (pinfunction "K_2") (pintype "passive"))
      (node (ref "S14_D3") (pin "1") (pinfunction "A_1") (pintype "passive"))
    )
    (net (code "31") (name "Net-(S15_C1-Positive)") (class "Default")
      (node (ref "S15_C1") (pin "1") (pinfunction "Positive_1") (pintype "power_in"))
      (node (ref "S15_C2") (pin "2") (pinfunction "Ground_2") (pintype "power_in"))
      (node (ref "S15_D1") (pin "2") (pinfunction "K_2") (pintype "passive"))
      (node (ref "S15_D2") (pin "1") (pinfunction "A_1") (pintype "passive"))
    )
    (net (code "32") (name "Net-(S15_C2-Positive)") (class "Default")
      (node (ref "S15_C2") (pin "1") (pinfunction "Positive_1") (pintype "power_in"))
      (node (ref "S15_D2") (pin "2") (pinfunction "K_2") (pintype "passive"))
      (node (ref "S15_D3") (pin "1") (pinfunction "A_1") (pintype "passive"))
    )
    (net (code "33") (name "Net-(S16_C1-Positive)") (class "Default")
      (node (ref "S16_C1") (pin "1") (pinfunction "Positive_1") (pintype "power_in"))
      (node (ref "S16_C2") (pin "2") (pinfunction "Ground_2") (pintype "power_in"))
      (node (ref "S16_D1") (pin "2") (pinfunction "K_2") (pintype "passive"))
      (node (ref "S16_D2") (pin "1") (pinfunction "A_1") (pintype "passive"))
    )
    (net (code "34") (name "Net-(S16_C2-Positive)") (class "Default")
      (node (ref "S16_C2") (pin "1") (pinfunction "Positive_1") (pintype "power_in"))
      (node (ref "S16_D2") (pin "2") (pinfunction "K_2") (pintype "passive"))
      (node (ref "S16_D3") (pin "1") (pinfunction "A_1") (pintype "passive"))
    )
    (net (code "35") (name "Net-(S17_C1-Positive)") (class "Default")
      (node (ref "S17_C1") (pin "1") (pinfunction "Positive_1") (pintype "power_in"))
      (node (ref "S17_C2") (pin "2") (pinfunction "Ground_2") (pintype "power_in"))
      (node (ref "S17_D1") (pin "2") (pinfunction "K_2") (pintype "passive"))
      (node (ref "S17_D2") (pin "1") (pinfunction "A_1") (pintype "passive"))
    )
    (net (code "36") (name "Net-(S17_C2-Positive)") (class "Default")
      (node (ref "S17_C2") (pin "1") (pinfunction "Positive_1") (pintype "power_in"))
      (node (ref "S17_D2") (pin "2") (pinfunction "K_2") (pintype "passive"))
      (node (ref "S17_D3") (pin "1") (pinfunction "A_1") (pintype "passive"))
    )
    (net (code "37") (name "Net-(S18_C1-Positive)") (class "Default")
      (node (ref "S18_C1") (pin "1") (pinfunction "Positive_1") (pintype "power_in"))
      (node (ref "S18_C2") (pin "2") (pinfunction "Ground_2") (pintype "power_in"))
      (node (ref "S18_D1") (pin "2") (pinfunction "K_2") (pintype "passive"))
      (node (ref "S18_D2") (pin "1") (pinfunction "A_1") (pintype "passive"))
    )
    (net (code "38") (name "Net-(S18_C2-Positive)") (class "Default")
      (node (ref "S18_C2") (pin "1") (pinfunction "Positive_1") (pintype "power_in"))
      (node (ref "S18_D2") (pin "2") (pinfunction "K_2") (pintype "passive"))
      (node (ref "S18_D3") (pin "1") (pinfunction "A_1") (pintype "passive"))
    )
    (net (code "39") (name "Net-(S19_C1-Positive)") (class "Default")
      (node (ref "S19_C1") (pin "1") (pinfunction "Positive_1") (pintype "power_in"))
      (node (ref "S19_C2") (pin "2") (pinfunction "Ground_2") (pintype "power_in"))
      (node (ref "S19_D1") (pin "2") (pinfunction "K_2") (pintype "passive"))
      (node (ref "S19_D2") (pin "1") (pinfunction "A_1") (pintype "passive"))
    )
    (net (code "40") (name "Net-(S19_C2-Positive)") (class "Default")
      (node (ref "S19_C2") (pin "1") (pinfunction "Positive_1") (pintype "power_in"))
      (node (ref "S19_D2") (pin "2") (pinfunction "K_2") (pintype "passive"))
      (node (ref "S19_D3") (pin "1") (pinfunction "A_1") (pintype "passive"))
    )
    (net (code "41") (name "Net-(S20_C1-Positive)") (class "Default")
      (node (ref "S20_C1") (pin "1") (pinfunction "Positive_1") (pintype "power_in"))
      (node (ref "S20_C2") (pin "2") (pinfunction "Ground_2") (pintype "power_in"))
      (node (ref "S20_D1") (pin "2") (pinfunction "K_2") (pintype "passive"))
      (node (ref "S20_D2") (pin "1") (pinfunction "A_1") (pintype "passive"))
    )
    (net (code "42") (name "Net-(S20_C2-Positive)") (class "Default")
      (node (ref "S20_C2") (pin "1") (pinfunction "Positive_1") (pintype "power_in"))
      (node (ref "S20_D2") (pin "2") (pinfunction "K_2") (pintype "passive"))
      (node (ref "S20_D3") (pin "1") (pinfunction "A_1") (pintype "passive"))
    )
    (net (code "43") (name "Net-(S21_C1-Positive)") (class "Default")
      (node (ref "S21_C1") (pin "1") (pinfunction "Positive_1") (pintype "power_in"))
      (node (ref "S21_C2") (pin "2") (pinfunction "Ground_2") (pintype "power_in"))
      (node (ref "S21_D1") (pin "2") (pinfunction "K_2") (pintype "passive"))
      (node (ref "S21_D2") (pin "1") (pinfunction "A_1") (pintype "passive"))
    )
    (net (code "44") (name "Net-(S21_C2-Positive)") (class "Default")
      (node (ref "S21_C2") (pin "1") (pinfunction "Positive_1") (pintype "power_in"))
      (node (ref "S21_D2") (pin "2") (pinfunction "K_2") (pintype "passive"))
      (node (ref "S21_D3") (pin "1") (pinfunction "A_1") (pintype "passive"))
    )
    (net (code "45") (name "Net-(S22_C1-Positive)") (class "Default")
      (node (ref "S22_C1") (pin "1") (pinfunction "Positive_1") (pintype "power_in"))
      (node (ref "S22_C2") (pin "2") (pinfunction "Ground_2") (pintype "power_in"))
      (node (ref "S22_D1") (pin "2") (pinfunction "K_2") (pintype "passive"))
      (node (ref "S22_D2") (pin "1") (pinfunction "A_1") (pintype "passive"))
    )
    (net (code "46") (name "Net-(S22_C2-Positive)") (class "Default")
      (node (ref "S22_C2") (pin "1") (pinfunction "Positive_1") (pintype "power_in"))
      (node (ref "S22_D2") (pin "2") (pinfunction "K_2") (pintype "passive"))
      (node (ref "S22_D3") (pin "1") (pinfunction "A_1") (pintype "passive"))
    )
    (net (code "47") (name "Net-(S23_C1-Positive)") (class "Default")
      (node (ref "S23_C1") (pin "1") (pinfunction "Positive_1") (pintype "power_in"))
      (node (ref "S23_C2") (pin "2") (pinfunction "Ground_2") (pintype "power_in"))
      (node (ref "S23_D1") (pin "2") (pinfunction "K_2") (pintype "passive"))
      (node (ref "S23_D2") (pin "1") (pinfunction "A_1") (pintype "passive"))
    )
    (net (code "48") (name "Net-(S23_C2-Positive)") (class "Default")
      (node (ref "S23_C2") (pin "1") (pinfunction "Positive_1") (pintype "power_in"))
      (node (ref "S23_D2") (pin "2") (pinfunction "K_2") (pintype "passive"))
      (node (ref "S23_D3") (pin "1") (pinfunction "A_1") (pintype "passive"))
    )
    (net (code "49") (name "Net-(S24_C1-Positive)") (class "Default")
      (node (ref "S24_C1") (pin "1") (pinfunction "Positive_1") (pintype "power_in"))
      (node (ref "S24_C2") (pin "2") (pinfunction "Ground_2") (pintype "power_in"))
      (node (ref "S24_D1") (pin "2") (pinfunction "K_2") (pintype "passive"))
      (node (ref "S24_D2") (pin "1") (pinfunction "A_1") (pintype "passive"))
    )
    (net (code "50") (name "Net-(S24_C2-Positive)") (class "Default")
      (node (ref "S24_C2") (pin "1") (pinfunction "Positive_1") (pintype "power_in"))
      (node (ref "S24_D2") (pin "2") (pinfunction "K_2") (pintype "passive"))
      (node (ref "S24_D3") (pin "1") (pinfunction "A_1") (pintype "passive"))
    )
  )
)
